# Controll_Board_2020-08-23_19-58-41.net
KiCad netlist of a schematic drawn in EasyEDA
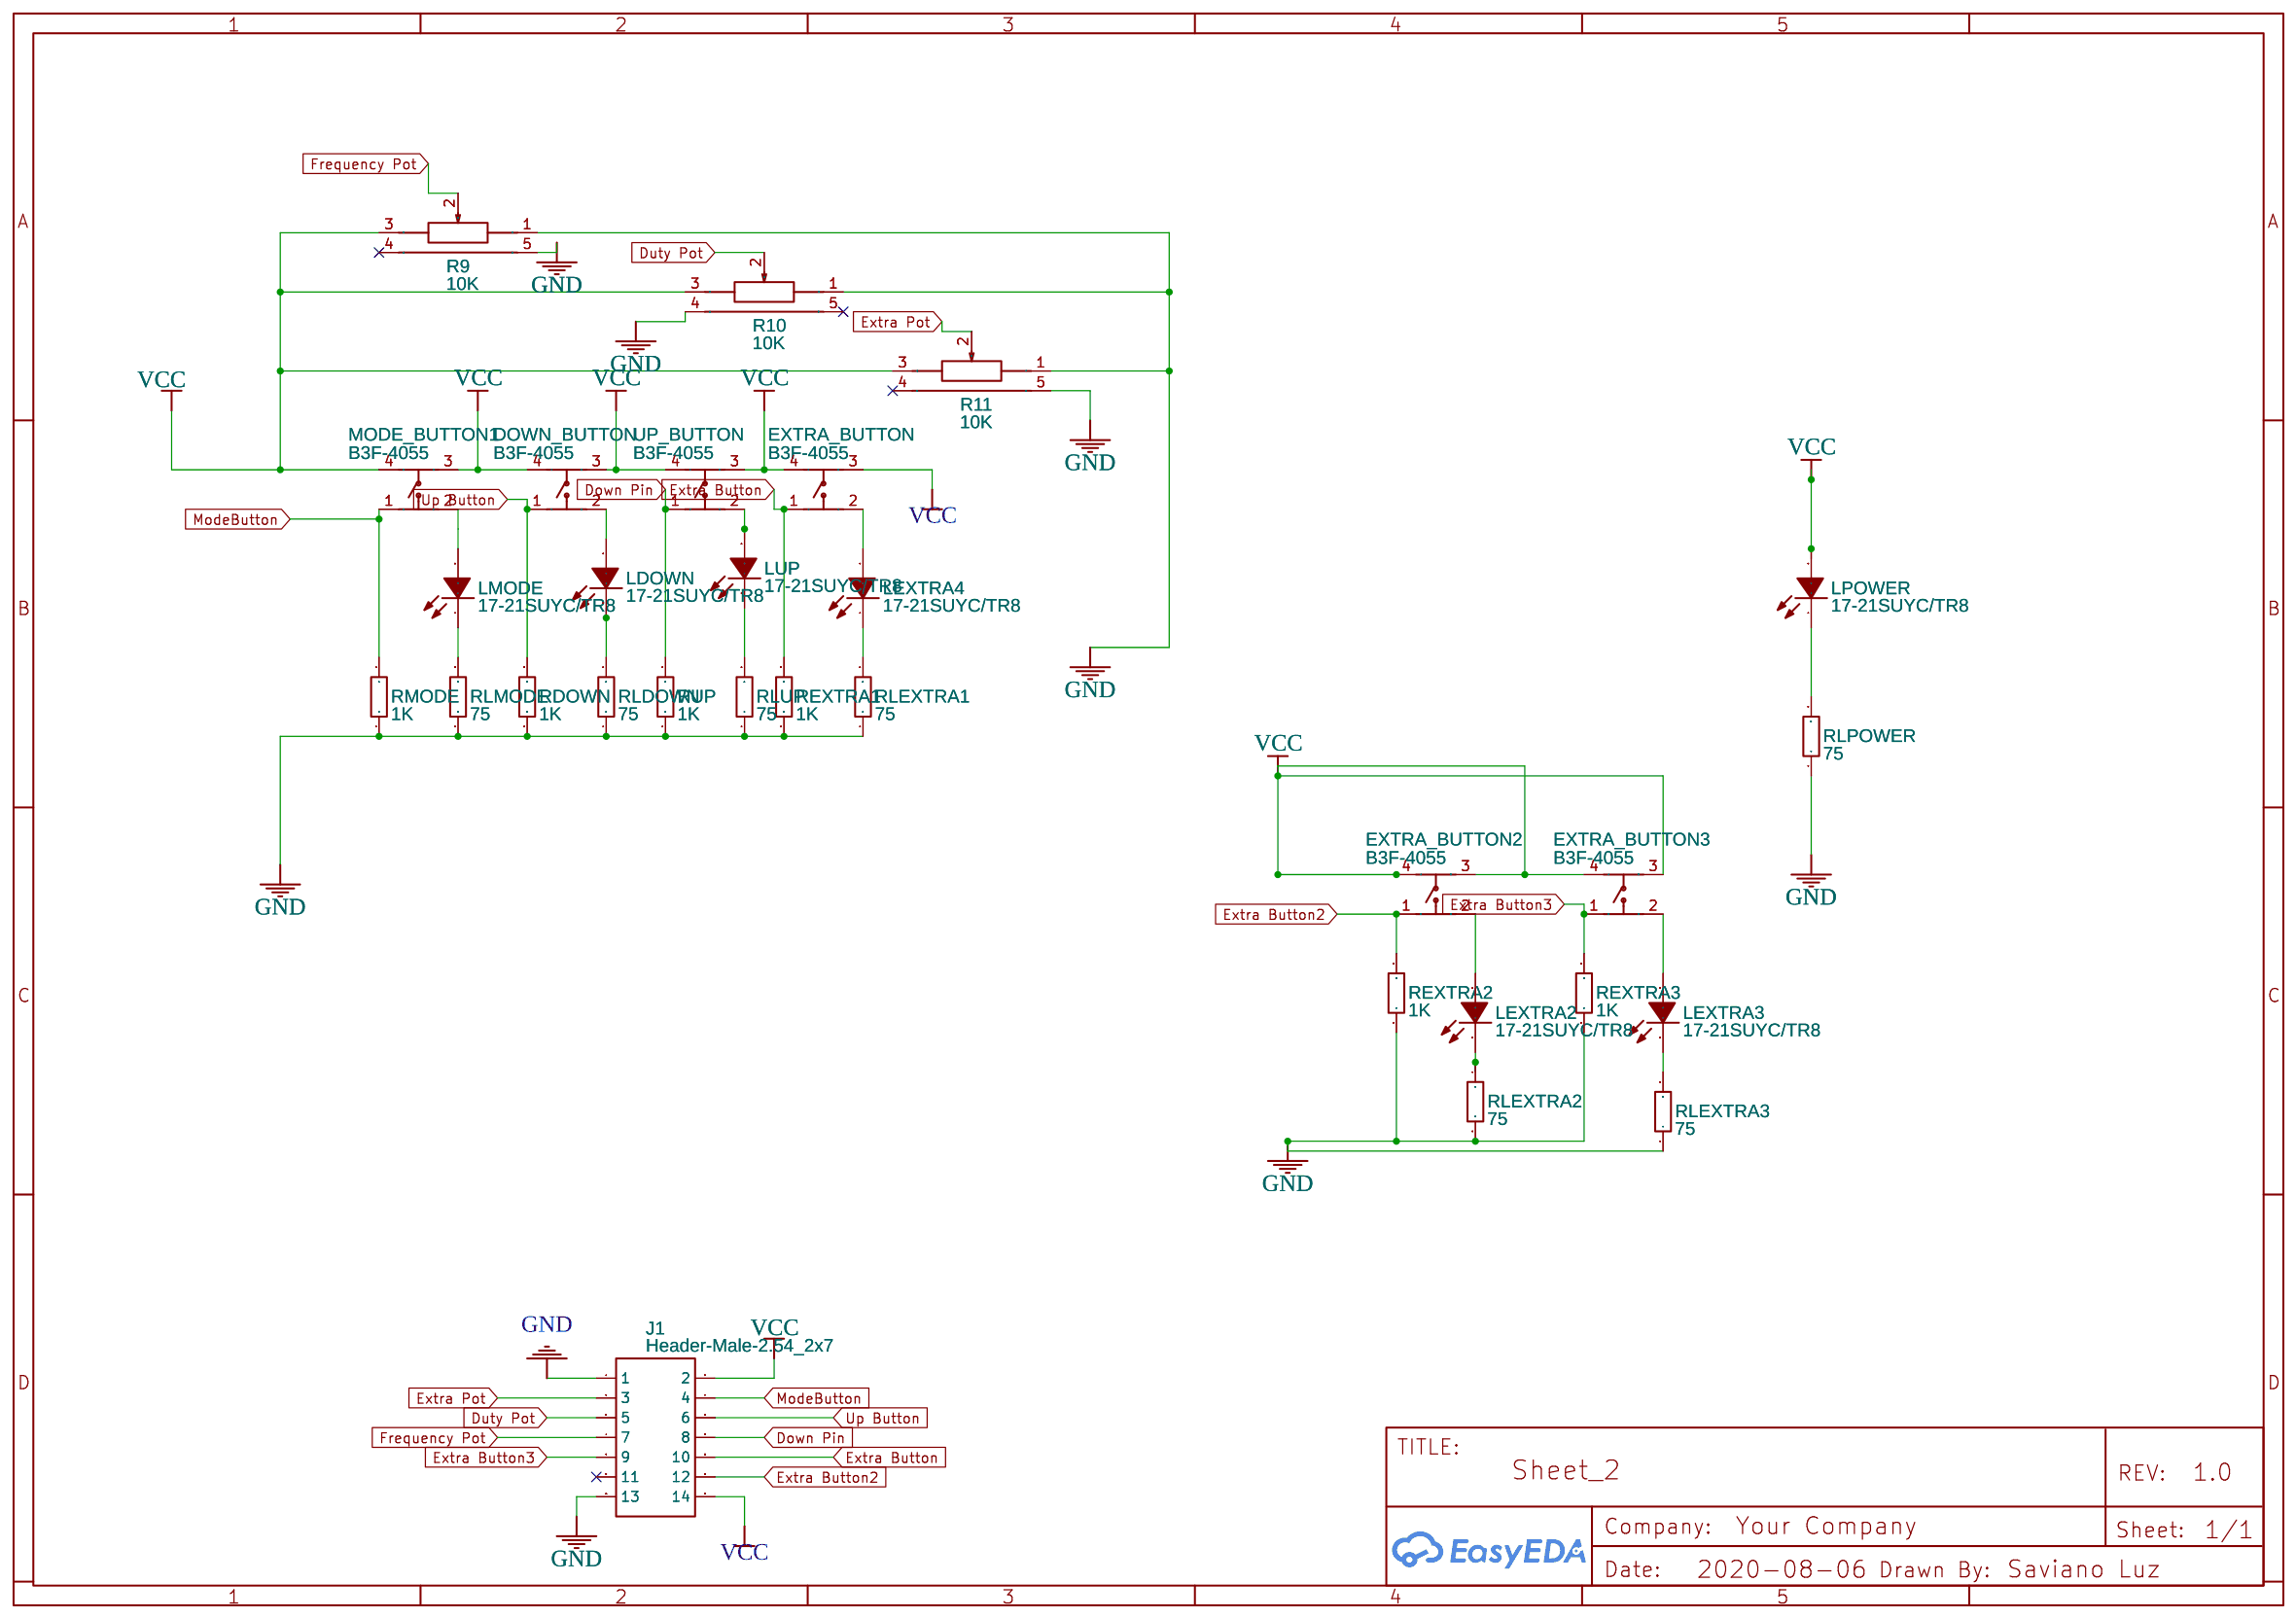
[diagram p0: schematic sheet]

(export (version "E")
  (design (tool "Eeschema 10.0.6"))
  (components
    (comp (ref "DOWN_BUTTON")
      (value "B3F-4055")
      (fields (field (name "BOM_Supplier Part") "C84931"))
      (libsource (lib "") (part "B3F-4055_1"))
    )
    (comp (ref "EXTRA_BUTTON")
      (value "B3F-4055")
      (fields (field (name "BOM_Supplier Part") "C84931"))
      (libsource (lib "") (part "B3F-4055_2"))
    )
    (comp (ref "EXTRA_BUTTON2")
      (value "B3F-4055")
      (fields (field (name "BOM_Supplier Part") "C84931"))
      (libsource (lib "") (part "B3F-4055_2"))
    )
    (comp (ref "EXTRA_BUTTON3")
      (value "B3F-4055")
      (fields (field (name "BOM_Supplier Part") "C84931"))
      (libsource (lib "") (part "B3F-4055_2"))
    )
    (comp (ref "J1")
      (value "Header-Male-2.54_2x7")
      (fields
        (field (name "BOM_Manufacturer Part") "Double row of needle2X7P 2.54mm")
        (field (name "BOM_Supplier Part") "C71397")
      )
      (libsource (lib "") (part "Header-Male-2.54_2x7"))
    )
    (comp (ref "LDOWN")
      (value "17-21SUYC/TR8")
      (fields (field (name "BOM_Supplier Part") "C2296"))
      (libsource (lib "") (part "17-21SUYC/TR8_4"))
    )
    (comp (ref "LEXTRA2")
      (value "17-21SUYC/TR8")
      (fields (field (name "BOM_Supplier Part") "C2296"))
      (libsource (lib "") (part "17-21SUYC/TR8_1"))
    )
    (comp (ref "LEXTRA3")
      (value "17-21SUYC/TR8")
      (fields (field (name "BOM_Supplier Part") "C2296"))
      (libsource (lib "") (part "17-21SUYC/TR8_1"))
    )
    (comp (ref "LEXTRA4")
      (value "17-21SUYC/TR8")
      (fields (field (name "BOM_Supplier Part") "C2296"))
      (libsource (lib "") (part "17-21SUYC/TR8_1"))
    )
    (comp (ref "LMODE")
      (value "17-21SUYC/TR8")
      (fields (field (name "BOM_Supplier Part") "C2296"))
      (libsource (lib "") (part "17-21SUYC/TR8_2"))
    )
    (comp (ref "LPOWER")
      (value "17-21SUYC/TR8")
      (fields (field (name "BOM_Supplier Part") "C2296"))
      (libsource (lib "") (part "17-21SUYC/TR8_3"))
    )
    (comp (ref "LUP")
      (value "17-21SUYC/TR8")
      (fields (field (name "BOM_Supplier Part") "C2296"))
      (libsource (lib "") (part "17-21SUYC/TR8"))
    )
    (comp (ref "MODE_BUTTON1")
      (value "B3F-4055")
      (fields (field (name "BOM_Supplier Part") "C84931"))
      (libsource (lib "") (part "B3F-4055_3"))
    )
    (comp (ref "R9")
      (value "10K")
      (fields
        (field (name "BOM_Manufacturer Part") "RK09K1130AAU")
        (field (name "BOM_Supplier Part") "C202373")
      )
      (libsource (lib "") (part "RK09K1130AAU"))
    )
    (comp (ref "R10")
      (value "10K")
      (fields
        (field (name "BOM_Manufacturer Part") "RK09K1130AAU")
        (field (name "BOM_Supplier Part") "C202373")
      )
      (libsource (lib "") (part "RK09K1130AAU"))
    )
    (comp (ref "R11")
      (value "10K")
      (fields
        (field (name "BOM_Manufacturer Part") "RK09K1130AAU")
        (field (name "BOM_Supplier Part") "C202373")
      )
      (libsource (lib "") (part "RK09K1130AAU"))
    )
    (comp (ref "RDOWN")
      (value "1K")
      (fields
        (field (name "BOM_Manufacturer Part") "0805W8F1001T5E")
        (field (name "BOM_Supplier Part") "C17513")
      )
      (libsource (lib "") (part "0805W8F1001T5E_3"))
    )
    (comp (ref "REXTRA1")
      (value "1K")
      (fields
        (field (name "BOM_Manufacturer Part") "0805W8F1001T5E")
        (field (name "BOM_Supplier Part") "C17513")
      )
      (libsource (lib "") (part "0805W8F1001T5E"))
    )
    (comp (ref "REXTRA2")
      (value "1K")
      (fields
        (field (name "BOM_Manufacturer Part") "0805W8F1001T5E")
        (field (name "BOM_Supplier Part") "C17513")
      )
      (libsource (lib "") (part "0805W8F1001T5E"))
    )
    (comp (ref "REXTRA3")
      (value "1K")
      (fields
        (field (name "BOM_Manufacturer Part") "0805W8F1001T5E")
        (field (name "BOM_Supplier Part") "C17513")
      )
      (libsource (lib "") (part "0805W8F1001T5E"))
    )
    (comp (ref "RLDOWN")
      (value "75")
      (fields
        (field (name "BOM_Manufacturer Part") "0805W8F750JT5E")
        (field (name "BOM_Supplier Part") "C20638")
      )
      (libsource (lib "") (part "0805W8F750JT5E_1"))
    )
    (comp (ref "RLEXTRA1")
      (value "75")
      (fields
        (field (name "BOM_Manufacturer Part") "0805W8F750JT5E")
        (field (name "BOM_Supplier Part") "C20638")
      )
      (libsource (lib "") (part "0805W8F750JT5E_2"))
    )
    (comp (ref "RLEXTRA2")
      (value "75")
      (fields
        (field (name "BOM_Manufacturer Part") "0805W8F750JT5E")
        (field (name "BOM_Supplier Part") "C20638")
      )
      (libsource (lib "") (part "0805W8F750JT5E_4"))
    )
    (comp (ref "RLEXTRA3")
      (value "75")
      (fields
        (field (name "BOM_Manufacturer Part") "0805W8F750JT5E")
        (field (name "BOM_Supplier Part") "C20638")
      )
      (libsource (lib "") (part "0805W8F750JT5E_2"))
    )
    (comp (ref "RLMODE")
      (value "75")
      (fields
        (field (name "BOM_Manufacturer Part") "0805W8F750JT5E")
        (field (name "BOM_Supplier Part") "C20638")
      )
      (libsource (lib "") (part "0805W8F750JT5E"))
    )
    (comp (ref "RLPOWER")
      (value "75")
      (fields
        (field (name "BOM_Manufacturer Part") "0805W8F750JT5E")
        (field (name "BOM_Supplier Part") "C20638")
      )
      (libsource (lib "") (part "0805W8F750JT5E_3"))
    )
    (comp (ref "RLUP")
      (value "75")
      (fields
        (field (name "BOM_Manufacturer Part") "0805W8F750JT5E")
        (field (name "BOM_Supplier Part") "C20638")
      )
      (libsource (lib "") (part "0805W8F750JT5E_5"))
    )
    (comp (ref "RMODE")
      (value "1K")
      (fields
        (field (name "BOM_Manufacturer Part") "0805W8F1001T5E")
        (field (name "BOM_Supplier Part") "C17513")
      )
      (libsource (lib "") (part "0805W8F1001T5E_2"))
    )
    (comp (ref "RUP")
      (value "1K")
      (fields
        (field (name "BOM_Manufacturer Part") "0805W8F1001T5E")
        (field (name "BOM_Supplier Part") "C17513")
      )
      (libsource (lib "") (part "0805W8F1001T5E_1"))
    )
    (comp (ref "UP_BUTTON")
      (value "B3F-4055")
      (fields (field (name "BOM_Supplier Part") "C84931"))
      (libsource (lib "") (part "B3F-4055"))
    )
  )
  (nets
    (net (code "1") (name "Down Pin") (class "Default")
      (node (ref "J1") (pin "8") (pinfunction "8_8") (pintype "input"))
      (node (ref "RUP") (pin "2") (pinfunction "2_2") (pintype "input"))
      (node (ref "UP_BUTTON") (pin "1") (pinfunction "1_1") (pintype "unspecified"))
    )
    (net (code "2") (name "Duty Pot") (class "Default")
      (node (ref "J1") (pin "5") (pinfunction "5_5") (pintype "input"))
      (node (ref "R10") (pin "2") (pinfunction "2_2") (pintype "unspecified"))
    )
    (net (code "3") (name "Extra Button") (class "Default")
      (node (ref "EXTRA_BUTTON") (pin "1") (pinfunction "1_1") (pintype "unspecified"))
      (node (ref "J1") (pin "10") (pinfunction "10_10") (pintype "input"))
      (node (ref "REXTRA1") (pin "2") (pinfunction "2_2") (pintype "input"))
    )
    (net (code "4") (name "Extra Button2") (class "Default")
      (node (ref "EXTRA_BUTTON2") (pin "1") (pinfunction "1_1") (pintype "unspecified"))
      (node (ref "J1") (pin "12") (pinfunction "12_12") (pintype "input"))
      (node (ref "REXTRA2") (pin "2") (pinfunction "2_2") (pintype "input"))
    )
    (net (code "5") (name "Extra Button3") (class "Default")
      (node (ref "EXTRA_BUTTON3") (pin "1") (pinfunction "1_1") (pintype "unspecified"))
      (node (ref "J1") (pin "9") (pinfunction "9_9") (pintype "input"))
      (node (ref "REXTRA3") (pin "2") (pinfunction "2_2") (pintype "input"))
    )
    (net (code "6") (name "Extra Pot") (class "Default")
      (node (ref "J1") (pin "3") (pinfunction "3_3") (pintype "input"))
      (node (ref "R11") (pin "2") (pinfunction "2_2") (pintype "unspecified"))
    )
    (net (code "7") (name "Frequency Pot") (class "Default")
      (node (ref "J1") (pin "7") (pinfunction "7_7") (pintype "input"))
      (node (ref "R9") (pin "2") (pinfunction "2_2") (pintype "unspecified"))
    )
    (net (code "8") (name "GND") (class "Default")
      (node (ref "J1") (pin "1") (pinfunction "1_1") (pintype "input"))
      (node (ref "J1") (pin "13") (pinfunction "13_13") (pintype "input"))
      (node (ref "R10") (pin "1") (pinfunction "1_1") (pintype "unspecified"))
      (node (ref "R10") (pin "4") (pinfunction "EH_4") (pintype "unspecified"))
      (node (ref "R11") (pin "1") (pinfunction "1_1") (pintype "unspecified"))
      (node (ref "R11") (pin "5") (pinfunction "EH_5") (pintype "unspecified"))
      (node (ref "R9") (pin "1") (pinfunction "1_1") (pintype "unspecified"))
      (node (ref "R9") (pin "5") (pinfunction "EH_5") (pintype "unspecified"))
      (node (ref "RDOWN") (pin "1") (pinfunction "1_1") (pintype "input"))
      (node (ref "REXTRA1") (pin "1") (pinfunction "1_1") (pintype "input"))
      (node (ref "REXTRA2") (pin "1") (pinfunction "1_1") (pintype "input"))
      (node (ref "REXTRA3") (pin "1") (pinfunction "1_1") (pintype "input"))
      (node (ref "RLDOWN") (pin "1") (pinfunction "1_1") (pintype "input"))
      (node (ref "RLEXTRA1") (pin "1") (pinfunction "1_1") (pintype "input"))
      (node (ref "RLEXTRA2") (pin "2") (pinfunction "2_2") (pintype "input"))
      (node (ref "RLEXTRA3") (pin "1") (pinfunction "1_1") (pintype "input"))
      (node (ref "RLMODE") (pin "1") (pinfunction "1_1") (pintype "input"))
      (node (ref "RLPOWER") (pin "1") (pinfunction "1_1") (pintype "input"))
      (node (ref "RLUP") (pin "1") (pinfunction "1_1") (pintype "input"))
      (node (ref "RMODE") (pin "1") (pinfunction "1_1") (pintype "input"))
      (node (ref "RUP") (pin "1") (pinfunction "1_1") (pintype "input"))
    )
    (net (code "9") (name "ModeButton") (class "Default")
      (node (ref "J1") (pin "4") (pinfunction "4_4") (pintype "input"))
      (node (ref "MODE_BUTTON1") (pin "1") (pinfunction "1_1") (pintype "unspecified"))
      (node (ref "RMODE") (pin "2") (pinfunction "2_2") (pintype "input"))
    )
    (net (code "10") (name "Net-(LDOWN-+)") (class "Default")
      (node (ref "DOWN_BUTTON") (pin "2") (pinfunction "2_2") (pintype "unspecified"))
      (node (ref "LDOWN") (pin "2") (pinfunction "+_2") (pintype "unspecified"))
    )
    (net (code "11") (name "Net-(LDOWN--)") (class "Default")
      (node (ref "LDOWN") (pin "1") (pinfunction "-_1") (pintype "unspecified"))
      (node (ref "RLDOWN") (pin "2") (pinfunction "2_2") (pintype "input"))
    )
    (net (code "12") (name "Net-(LEXTRA2-+)") (class "Default")
      (node (ref "EXTRA_BUTTON2") (pin "2") (pinfunction "2_2") (pintype "unspecified"))
      (node (ref "LEXTRA2") (pin "2") (pinfunction "+_2") (pintype "unspecified"))
    )
    (net (code "13") (name "Net-(LEXTRA2--)") (class "Default")
      (node (ref "LEXTRA2") (pin "1") (pinfunction "-_1") (pintype "unspecified"))
      (node (ref "RLEXTRA2") (pin "1") (pinfunction "1_1") (pintype "input"))
    )
    (net (code "14") (name "Net-(LEXTRA3-+)") (class "Default")
      (node (ref "EXTRA_BUTTON3") (pin "2") (pinfunction "2_2") (pintype "unspecified"))
      (node (ref "LEXTRA3") (pin "2") (pinfunction "+_2") (pintype "unspecified"))
    )
    (net (code "15") (name "Net-(LEXTRA3--)") (class "Default")
      (node (ref "LEXTRA3") (pin "1") (pinfunction "-_1") (pintype "unspecified"))
      (node (ref "RLEXTRA3") (pin "2") (pinfunction "2_2") (pintype "input"))
    )
    (net (code "16") (name "Net-(LEXTRA4-+)") (class "Default")
      (node (ref "EXTRA_BUTTON") (pin "2") (pinfunction "2_2") (pintype "unspecified"))
      (node (ref "LEXTRA4") (pin "2") (pinfunction "+_2") (pintype "unspecified"))
    )
    (net (code "17") (name "Net-(LEXTRA4--)") (class "Default")
      (node (ref "LEXTRA4") (pin "1") (pinfunction "-_1") (pintype "unspecified"))
      (node (ref "RLEXTRA1") (pin "2") (pinfunction "2_2") (pintype "input"))
    )
    (net (code "18") (name "Net-(LMODE-+)") (class "Default")
      (node (ref "LMODE") (pin "2") (pinfunction "+_2") (pintype "unspecified"))
      (node (ref "MODE_BUTTON1") (pin "2") (pinfunction "2_2") (pintype "unspecified"))
    )
    (net (code "19") (name "Net-(LMODE--)") (class "Default")
      (node (ref "LMODE") (pin "1") (pinfunction "-_1") (pintype "unspecified"))
      (node (ref "RLMODE") (pin "2") (pinfunction "2_2") (pintype "input"))
    )
    (net (code "20") (name "Net-(LPOWER--)") (class "Default")
      (node (ref "LPOWER") (pin "1") (pinfunction "-_1") (pintype "unspecified"))
      (node (ref "RLPOWER") (pin "2") (pinfunction "2_2") (pintype "input"))
    )
    (net (code "21") (name "Net-(LUP-+)") (class "Default")
      (node (ref "LUP") (pin "2") (pinfunction "+_2") (pintype "unspecified"))
      (node (ref "UP_BUTTON") (pin "2") (pinfunction "2_2") (pintype "unspecified"))
    )
    (net (code "22") (name "Net-(LUP--)") (class "Default")
      (node (ref "LUP") (pin "1") (pinfunction "-_1") (pintype "unspecified"))
      (node (ref "RLUP") (pin "2") (pinfunction "2_2") (pintype "input"))
    )
    (net (code "23") (name "Up Button") (class "Default")
      (node (ref "DOWN_BUTTON") (pin "1") (pinfunction "1_1") (pintype "unspecified"))
      (node (ref "J1") (pin "6") (pinfunction "6_6") (pintype "input"))
      (node (ref "RDOWN") (pin "2") (pinfunction "2_2") (pintype "input"))
    )
    (net (code "24") (name "VCC") (class "Default")
      (node (ref "DOWN_BUTTON") (pin "3") (pinfunction "3_3") (pintype "unspecified"))
      (node (ref "DOWN_BUTTON") (pin "4") (pinfunction "4_4") (pintype "unspecified"))
      (node (ref "EXTRA_BUTTON") (pin "3") (pinfunction "3_3") (pintype "unspecified"))
      (node (ref "EXTRA_BUTTON") (pin "4") (pinfunction "4_4") (pintype "unspecified"))
      (node (ref "EXTRA_BUTTON2") (pin "3") (pinfunction "3_3") (pintype "unspecified"))
      (node (ref "EXTRA_BUTTON2") (pin "4") (pinfunction "4_4") (pintype "unspecified"))
      (node (ref "EXTRA_BUTTON3") (pin "3") (pinfunction "3_3") (pintype "unspecified"))
      (node (ref "EXTRA_BUTTON3") (pin "4") (pinfunction "4_4") (pintype "unspecified"))
      (node (ref "J1") (pin "14") (pinfunction "14_14") (pintype "input"))
      (node (ref "J1") (pin "2") (pinfunction "2_2") (pintype "input"))
      (node (ref "LPOWER") (pin "2") (pinfunction "+_2") (pintype "unspecified"))
      (node (ref "MODE_BUTTON1") (pin "3") (pinfunction "3_3") (pintype "unspecified"))
      (node (ref "MODE_BUTTON1") (pin "4") (pinfunction "4_4") (pintype "unspecified"))
      (node (ref "R10") (pin "3") (pinfunction "3_3") (pintype "unspecified"))
      (node (ref "R11") (pin "3") (pinfunction "3_3") (pintype "unspecified"))
      (node (ref "R9") (pin "3") (pinfunction "3_3") (pintype "unspecified"))
      (node (ref "UP_BUTTON") (pin "3") (pinfunction "3_3") (pintype "unspecified"))
      (node (ref "UP_BUTTON") (pin "4") (pinfunction "4_4") (pintype "unspecified"))
    )
    (net (code "25") (name "unconnected-(J1-Pad11)") (class "Default")
      (node (ref "J1") (pin "11") (pinfunction "11_11") (pintype "input+no_connect"))
    )
    (net (code "26") (name "unconnected-(R9-EH-Pad4)") (class "Default")
      (node (ref "R9") (pin "4") (pinfunction "EH_4") (pintype "unspecified+no_connect"))
    )
    (net (code "27") (name "unconnected-(R10-EH-Pad5)") (class "Default")
      (node (ref "R10") (pin "5") (pinfunction "EH_5") (pintype "unspecified+no_connect"))
    )
    (net (code "28") (name "unconnected-(R11-EH-Pad4)") (class "Default")
      (node (ref "R11") (pin "4") (pinfunction "EH_4") (pintype "unspecified+no_connect"))
    )
  )
)
